# transister_as_switch.net
KiCad netlist of a schematic drawn in EAGLE
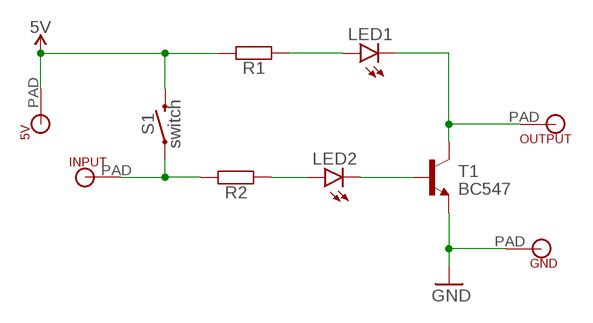
[diagram p0: schematic, sheet 1]

(export (version "E")
  (design (tool "Eeschema 10.0.6"))
  (components
    (comp (ref "5V")
      (value "MICROBIT_PAD")
      (footprint "eagle-import:MICROBIT_PAD")
      (libsource (lib "eagle-import") (part "MICROBIT_PAD"))
    )
    (comp (ref "GND")
      (value "MICROBIT_PAD")
      (footprint "eagle-import:MICROBIT_PAD")
      (libsource (lib "eagle-import") (part "MICROBIT_PAD"))
    )
    (comp (ref "INPUT")
      (value "MICROBIT_PAD")
      (footprint "eagle-import:MICROBIT_PAD")
      (libsource (lib "eagle-import") (part "MICROBIT_PAD"))
    )
    (comp (ref "LED1")
      (value "LEDCHIP-LED0805")
      (footprint "eagle-import:CHIP-LED0805")
      (libsource (lib "eagle-import") (part "LEDCHIP-LED0805"))
    )
    (comp (ref "LED2")
      (value "LEDCHIP-LED0805")
      (footprint "eagle-import:CHIP-LED0805")
      (libsource (lib "eagle-import") (part "LEDCHIP-LED0805"))
    )
    (comp (ref "OUTPUT")
      (value "MICROBIT_PAD")
      (footprint "eagle-import:MICROBIT_PAD")
      (libsource (lib "eagle-import") (part "MICROBIT_PAD"))
    )
    (comp (ref "R1")
      (value "RESISTOR-07")
      (footprint "eagle-import:R0207_7")
      (libsource (lib "eagle-import") (part "RESISTOR-07"))
    )
    (comp (ref "R2")
      (value "RESISTOR-07")
      (footprint "eagle-import:R0207_7")
      (libsource (lib "eagle-import") (part "RESISTOR-07"))
    )
    (comp (ref "S1")
      (value "switch")
      (footprint "eagle-import:TACTILE_SWITCH_PTH_6.0MM")
      (libsource (lib "eagle-import") (part "MOMENTARY-SWITCH-SPST-PTH-6.0MM"))
    )
    (comp (ref "T1")
      (value "BC547")
      (footprint "eagle-import:TO92")
      (libsource (lib "eagle-import") (part "BC547"))
    )
  )
  (nets
    (net (code "1") (name "5V") (class "Default")
      (node (ref "5V") (pin "PAD") (pinfunction "P$1_PAD") (pintype "bidirectional"))
      (node (ref "R1") (pin "2") (pinfunction "2_2") (pintype "passive"))
      (node (ref "S1") (pin "3") (pinfunction "2_3") (pintype "passive"))
    )
    (net (code "2") (name "GND") (class "Default")
      (node (ref "GND") (pin "PAD") (pinfunction "P$1_PAD") (pintype "bidirectional"))
      (node (ref "T1") (pin "1") (pinfunction "E_1") (pintype "passive"))
    )
    (net (code "3") (name "Net-(INPUT-P$1)") (class "Default")
      (node (ref "INPUT") (pin "PAD") (pinfunction "P$1_PAD") (pintype "bidirectional"))
      (node (ref "R2") (pin "2") (pinfunction "2_2") (pintype "passive"))
      (node (ref "S1") (pin "1") (pinfunction "1_1") (pintype "passive"))
    )
    (net (code "4") (name "Net-(LED1-PadA)") (class "Default")
      (node (ref "LED1") (pin "A") (pinfunction "A_A") (pintype "passive"))
      (node (ref "R1") (pin "1") (pinfunction "1_1") (pintype "passive"))
    )
    (net (code "5") (name "Net-(LED2-PadA)") (class "Default")
      (node (ref "LED2") (pin "A") (pinfunction "A_A") (pintype "passive"))
      (node (ref "R2") (pin "1") (pinfunction "1_1") (pintype "passive"))
    )
    (net (code "6") (name "Net-(OUTPUT-P$1)") (class "Default")
      (node (ref "LED1") (pin "C") (pinfunction "C_C") (pintype "passive"))
      (node (ref "OUTPUT") (pin "PAD") (pinfunction "P$1_PAD") (pintype "bidirectional"))
      (node (ref "T1") (pin "3") (pinfunction "C_3") (pintype "passive"))
    )
    (net (code "7") (name "Net-(T1-B)") (class "Default")
      (node (ref "LED2") (pin "C") (pinfunction "C_C") (pintype "passive"))
      (node (ref "T1") (pin "2") (pinfunction "B_2") (pintype "passive"))
    )
  )
)
